# HumNet.net
KiCad netlist of a schematic drawn in Altium Designer
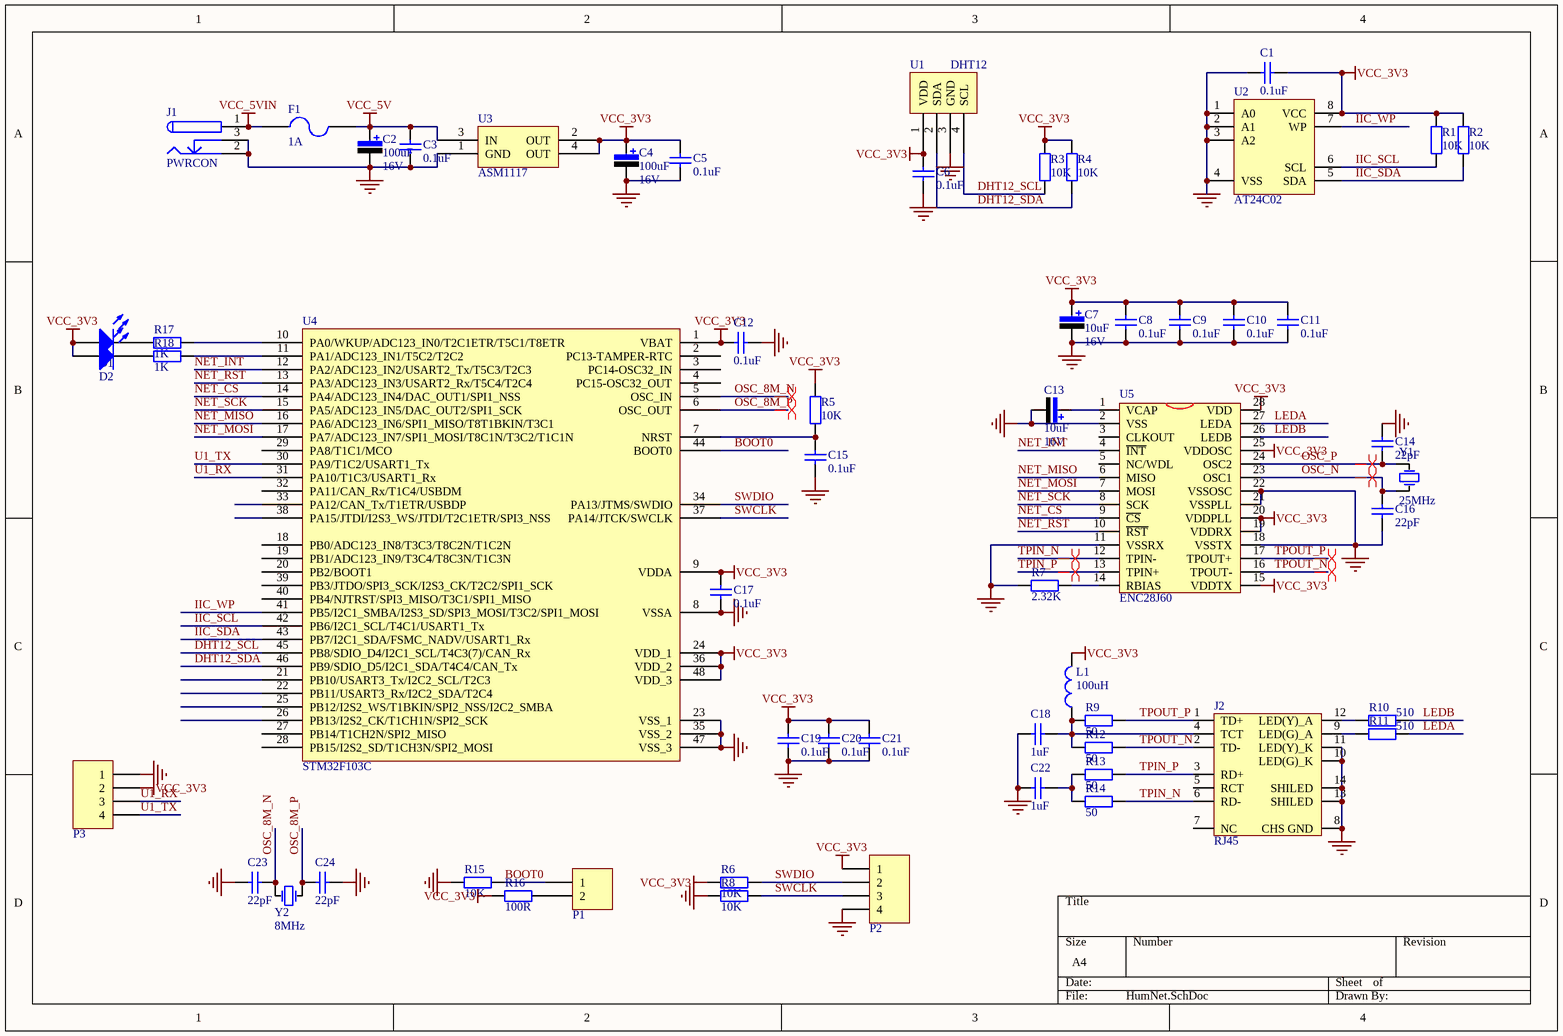
[diagram p0: HumNet.SchDoc]

(export (version "E")
  (design (tool "Eeschema 10.0.6"))
  (components
    (comp (ref "C1")
      (value "0.1uF")
      (footprint "C-RAD-0603")
      (description "无极性电容")
      (fields (field (name "Comment") "Cap") (field (name "PUBLISHER") "Altium Limited"))
      (libsource (lib "fszhang") (part "Cap"))
    )
    (comp (ref "C2")
      (value "100uF")
      (footprint "CAP-3528")
      (description "极性电解电容")
      (fields
        (field (name "VOL") "16V")
        (field (name "Comment") "Cap Pol")
        (field (name "PUBLISHER") "Altium Limited")
      )
      (libsource (lib "fszhang") (part "Cap Pol"))
    )
    (comp (ref "C3")
      (value "0.1uF")
      (footprint "C-RAD-0603")
      (description "无极性电容")
      (fields (field (name "Comment") "Cap") (field (name "PUBLISHER") "Altium Limited"))
      (libsource (lib "fszhang") (part "Cap"))
    )
    (comp (ref "C4")
      (value "100uF")
      (footprint "CAP-3528")
      (description "极性电解电容")
      (fields
        (field (name "VOL") "16V")
        (field (name "Comment") "Cap Pol")
        (field (name "PUBLISHER") "Altium Limited")
      )
      (libsource (lib "fszhang") (part "Cap Pol"))
    )
    (comp (ref "C5")
      (value "0.1uF")
      (footprint "C-RAD-0603")
      (description "无极性电容")
      (fields (field (name "Comment") "Cap") (field (name "PUBLISHER") "Altium Limited"))
      (libsource (lib "fszhang") (part "Cap"))
    )
    (comp (ref "C6")
      (value "0.1uF")
      (footprint "C-RAD-0603")
      (description "无极性电容")
      (fields (field (name "Comment") "Cap") (field (name "PUBLISHER") "Altium Limited"))
      (libsource (lib "fszhang") (part "Cap"))
    )
    (comp (ref "C7")
      (value "10uF")
      (footprint "CAP-3528")
      (description "极性电解电容")
      (fields
        (field (name "VOL") "16V")
        (field (name "Comment") "Cap Pol")
        (field (name "PUBLISHER") "Altium Limited")
      )
      (libsource (lib "fszhang") (part "Cap Pol"))
    )
    (comp (ref "C8")
      (value "0.1uF")
      (footprint "C-RAD-0603")
      (description "无极性电容")
      (fields (field (name "Comment") "Cap") (field (name "PUBLISHER") "Altium Limited"))
      (libsource (lib "fszhang") (part "Cap"))
    )
    (comp (ref "C9")
      (value "0.1uF")
      (footprint "C-RAD-0603")
      (description "无极性电容")
      (fields (field (name "Comment") "Cap") (field (name "PUBLISHER") "Altium Limited"))
      (libsource (lib "fszhang") (part "Cap"))
    )
    (comp (ref "C10")
      (value "0.1uF")
      (footprint "C-RAD-0603")
      (description "无极性电容")
      (fields (field (name "Comment") "Cap") (field (name "PUBLISHER") "Altium Limited"))
      (libsource (lib "fszhang") (part "Cap"))
    )
    (comp (ref "C11")
      (value "0.1uF")
      (footprint "C-RAD-0603")
      (description "无极性电容")
      (fields (field (name "Comment") "Cap") (field (name "PUBLISHER") "Altium Limited"))
      (libsource (lib "fszhang") (part "Cap"))
    )
    (comp (ref "C12")
      (value "0.1uF")
      (footprint "C-RAD-0603")
      (description "无极性电容")
      (fields (field (name "Comment") "Cap") (field (name "PUBLISHER") "Altium Limited"))
      (libsource (lib "fszhang") (part "Cap"))
    )
    (comp (ref "C13")
      (value "10uF")
      (footprint "CAP-3528")
      (description "极性电解电容")
      (fields
        (field (name "VOL") "16V")
        (field (name "Comment") "Cap Pol")
        (field (name "PUBLISHER") "Altium Limited")
      )
      (libsource (lib "") (part "Cap Pol_1"))
    )
    (comp (ref "C14")
      (value "22pF")
      (footprint "C-RAD-0603")
      (description "无极性电容")
      (fields (field (name "Comment") "Cap") (field (name "PUBLISHER") "Altium Limited"))
      (libsource (lib "fszhang") (part "Cap"))
    )
    (comp (ref "C15")
      (value "0.1uF")
      (footprint "C-RAD-0603")
      (description "无极性电容")
      (fields (field (name "Comment") "Cap") (field (name "PUBLISHER") "Altium Limited"))
      (libsource (lib "fszhang") (part "Cap"))
    )
    (comp (ref "C16")
      (value "22pF")
      (footprint "C-RAD-0603")
      (description "无极性电容")
      (fields (field (name "Comment") "Cap") (field (name "PUBLISHER") "Altium Limited"))
      (libsource (lib "fszhang") (part "Cap"))
    )
    (comp (ref "C17")
      (value "0.1uF")
      (footprint "C-RAD-0603")
      (description "无极性电容")
      (fields (field (name "Comment") "Cap") (field (name "PUBLISHER") "Altium Limited"))
      (libsource (lib "fszhang") (part "Cap"))
    )
    (comp (ref "C18")
      (value "1uF")
      (footprint "C-RAD-0603")
      (description "无极性电容")
      (fields (field (name "Comment") "Cap") (field (name "PUBLISHER") "Altium Limited"))
      (libsource (lib "fszhang") (part "Cap"))
    )
    (comp (ref "C19")
      (value "0.1uF")
      (footprint "C-RAD-0603")
      (description "无极性电容")
      (fields (field (name "Comment") "Cap") (field (name "PUBLISHER") "Altium Limited"))
      (libsource (lib "fszhang") (part "Cap"))
    )
    (comp (ref "C20")
      (value "0.1uF")
      (footprint "C-RAD-0603")
      (description "无极性电容")
      (fields (field (name "Comment") "Cap") (field (name "PUBLISHER") "Altium Limited"))
      (libsource (lib "fszhang") (part "Cap"))
    )
    (comp (ref "C21")
      (value "0.1uF")
      (footprint "C-RAD-0603")
      (description "无极性电容")
      (fields (field (name "Comment") "Cap") (field (name "PUBLISHER") "Altium Limited"))
      (libsource (lib "fszhang") (part "Cap"))
    )
    (comp (ref "C22")
      (value "1uF")
      (footprint "C-RAD-0603")
      (description "无极性电容")
      (fields (field (name "Comment") "Cap") (field (name "PUBLISHER") "Altium Limited"))
      (libsource (lib "fszhang") (part "Cap"))
    )
    (comp (ref "C23")
      (value "22pF")
      (footprint "C-RAD-0603")
      (description "无极性电容")
      (fields (field (name "Comment") "Cap") (field (name "PUBLISHER") "Altium Limited"))
      (libsource (lib "fszhang") (part "Cap"))
    )
    (comp (ref "C24")
      (value "22pF")
      (footprint "C-RAD-0603")
      (description "无极性电容")
      (fields (field (name "Comment") "Cap") (field (name "PUBLISHER") "Altium Limited"))
      (libsource (lib "fszhang") (part "Cap"))
    )
    (comp (ref "D1")
      (value "LED0")
      (footprint "LED_0805")
      (description "发光二极管")
      (fields (field (name "PUBLISHER") "Altium Limited"))
      (libsource (lib "fszhang") (part "LED0"))
    )
    (comp (ref "D2")
      (value "LED0")
      (footprint "LED_0805")
      (description "发光二极管")
      (fields (field (name "PUBLISHER") "Altium Limited"))
      (libsource (lib "fszhang") (part "LED0"))
    )
    (comp (ref "F1")
      (value "1A")
      (footprint "1812")
      (description "保险丝")
      (fields (field (name "Comment") "Fuse") (field (name "PUBLISHER") "Altium Limited"))
      (libsource (lib "fszhang") (part "Fuse 2"))
    )
    (comp (ref "J1")
      (value "PWRCON")
      (footprint "DC-005")
      (description "直流电源端子")
      (fields (field (name "PUBLISHER") "Altium Limited"))
      (libsource (lib "fszhang") (part "PWRCON"))
    )
    (comp (ref "J2")
      (value "RJ45")
      (footprint "HR911105A")
      (libsource (lib "ENC28J60网络模块封装库") (part "HR911105"))
    )
    (comp (ref "L1")
      (value "100uH")
      (footprint "1206")
      (description "电感")
      (fields (field (name "Comment") "Inductor") (field (name "PUBLISHER") "Altium Limited"))
      (libsource (lib "fszhang") (part "Inductor"))
    )
    (comp (ref "P1")
      (value "Header 2")
      (footprint "HDR2X1_A")
      (description "接插件")
      (fields (field (name "PUBLISHER") "Altium Limited"))
      (libsource (lib "fszhang") (part "Header 2"))
    )
    (comp (ref "P2")
      (value "Header 4")
      (footprint "HDR4X1_A")
      (description "接插件")
      (fields (field (name "PUBLISHER") "Altium Limited"))
      (libsource (lib "fszhang") (part "Header 4"))
    )
    (comp (ref "P3")
      (value "Header 4")
      (footprint "HDR4X1_A")
      (description "接插件")
      (fields (field (name "PUBLISHER") "Altium Limited"))
      (libsource (lib "") (part "Header 4_1"))
    )
    (comp (ref "R1")
      (value "10K")
      (footprint "0603-1")
      (description "贴片电阻")
      (fields (field (name "Comment") "Res1") (field (name "PUBLISHER") "Altium Limited"))
      (libsource (lib "") (part "Res1_1"))
    )
    (comp (ref "R2")
      (value "10K")
      (footprint "0603-1")
      (description "贴片电阻")
      (fields (field (name "Comment") "Res1") (field (name "PUBLISHER") "Altium Limited"))
      (libsource (lib "") (part "Res1_1"))
    )
    (comp (ref "R3")
      (value "10K")
      (footprint "0603-1")
      (description "贴片电阻")
      (fields (field (name "Comment") "Res1") (field (name "PUBLISHER") "Altium Limited"))
      (libsource (lib "") (part "Res1_1"))
    )
    (comp (ref "R4")
      (value "10K")
      (footprint "0603-1")
      (description "贴片电阻")
      (fields (field (name "Comment") "Res1") (field (name "PUBLISHER") "Altium Limited"))
      (libsource (lib "") (part "Res1_1"))
    )
    (comp (ref "R5")
      (value "10K")
      (footprint "0603-1")
      (description "贴片电阻")
      (fields (field (name "Comment") "Res1") (field (name "PUBLISHER") "Altium Limited"))
      (libsource (lib "") (part "Res1_1"))
    )
    (comp (ref "R6")
      (value "10K")
      (footprint "0603-1")
      (description "贴片电阻")
      (fields (field (name "Comment") "Res1") (field (name "PUBLISHER") "Altium Limited"))
      (libsource (lib "fszhang") (part "Res1"))
    )
    (comp (ref "R7")
      (value "2.32K")
      (footprint "0603-1")
      (description "贴片电阻")
      (fields (field (name "Comment") "Res1") (field (name "PUBLISHER") "Altium Limited"))
      (libsource (lib "fszhang") (part "Res1"))
    )
    (comp (ref "R8")
      (value "10K")
      (footprint "0603-1")
      (description "贴片电阻")
      (fields (field (name "Comment") "Res1") (field (name "PUBLISHER") "Altium Limited"))
      (libsource (lib "fszhang") (part "Res1"))
    )
    (comp (ref "R9")
      (value "50")
      (footprint "0603-1")
      (description "贴片电阻")
      (fields (field (name "Comment") "Res1") (field (name "PUBLISHER") "Altium Limited"))
      (libsource (lib "fszhang") (part "Res1"))
    )
    (comp (ref "R10")
      (value "510")
      (footprint "0603-1")
      (description "贴片电阻")
      (fields (field (name "Comment") "Res1") (field (name "PUBLISHER") "Altium Limited"))
      (libsource (lib "fszhang") (part "Res1"))
    )
    (comp (ref "R11")
      (value "510")
      (footprint "0603-1")
      (description "贴片电阻")
      (fields (field (name "Comment") "Res1") (field (name "PUBLISHER") "Altium Limited"))
      (libsource (lib "fszhang") (part "Res1"))
    )
    (comp (ref "R12")
      (value "50")
      (footprint "0603-1")
      (description "贴片电阻")
      (fields (field (name "Comment") "Res1") (field (name "PUBLISHER") "Altium Limited"))
      (libsource (lib "fszhang") (part "Res1"))
    )
    (comp (ref "R13")
      (value "50")
      (footprint "0603-1")
      (description "贴片电阻")
      (fields (field (name "Comment") "Res1") (field (name "PUBLISHER") "Altium Limited"))
      (libsource (lib "fszhang") (part "Res1"))
    )
    (comp (ref "R14")
      (value "50")
      (footprint "0603-1")
      (description "贴片电阻")
      (fields (field (name "Comment") "Res1") (field (name "PUBLISHER") "Altium Limited"))
      (libsource (lib "fszhang") (part "Res1"))
    )
    (comp (ref "R15")
      (value "10K")
      (footprint "0603-1")
      (description "贴片电阻")
      (fields (field (name "Comment") "Res1") (field (name "PUBLISHER") "Altium Limited"))
      (libsource (lib "fszhang") (part "Res1"))
    )
    (comp (ref "R16")
      (value "100R")
      (footprint "0603-1")
      (description "贴片电阻")
      (fields (field (name "Comment") "Res1") (field (name "PUBLISHER") "Altium Limited"))
      (libsource (lib "fszhang") (part "Res1"))
    )
    (comp (ref "R17")
      (value "1K")
      (footprint "0603-1")
      (description "贴片电阻")
      (fields (field (name "Comment") "Res1") (field (name "PUBLISHER") "Altium Limited"))
      (libsource (lib "fszhang") (part "Res1"))
    )
    (comp (ref "R18")
      (value "1K")
      (footprint "0603-1")
      (description "贴片电阻")
      (fields (field (name "Comment") "Res1") (field (name "PUBLISHER") "Altium Limited"))
      (libsource (lib "fszhang") (part "Res1"))
    )
    (comp (ref "U1") (value "DHT12") (footprint "DHT11") (libsource (lib "KS-D01") (part "DHT12")))
    (comp (ref "U2")
      (value "AT24C02")
      (footprint "SOIC8_N")
      (description "EEROM存储器")
      (libsource (lib "fszhang") (part "AT24C02"))
    )
    (comp (ref "U3")
      (value "ASM1117")
      (footprint "SOT-223")
      (description "3.3V稳压芯片")
      (libsource (lib "fszhang") (part "ASM1117"))
    )
    (comp (ref "U4")
      (value "STM32F103C")
      (footprint "LQFP-48_M")
      (description "STM32单片机48引脚")
      (libsource (lib "fszhang") (part "STM32F103C"))
    )
    (comp (ref "U5")
      (value "ENC28J60")
      (footprint "SSOP28")
      (libsource (lib "ENC28J60网络模块封装库") (part "ENC28J60"))
    )
    (comp (ref "Y1")
      (value "25MHz")
      (footprint "X-SM49")
      (description "晶振")
      (fields (field (name "Comment") "XTAL") (field (name "PUBLISHER") "Altium Limited"))
      (libsource (lib "fszhang") (part "XTAL"))
    )
    (comp (ref "Y2")
      (value "8MHz")
      (footprint "X-SM49")
      (description "晶振")
      (fields (field (name "Comment") "XTAL") (field (name "PUBLISHER") "Altium Limited"))
      (libsource (lib "fszhang") (part "XTAL"))
    )
  )
  (nets
    (net (code "1") (name "/BOOT0") (class "Default")
      (node (ref "P1") (pin "1") (pinfunction "1_1") (pintype "passive"))
      (node (ref "R15") (pin "2") (pinfunction "2_2") (pintype "passive"))
      (node (ref "U4") (pin "44") (pinfunction "BOOT0_44") (pintype "passive"))
    )
    (net (code "2") (name "/DHT12_SCL") (class "Default")
      (node (ref "R3") (pin "1") (pinfunction "1_1") (pintype "passive"))
      (node (ref "U1") (pin "4") (pinfunction "SCL_4") (pintype "passive"))
      (node (ref "U4") (pin "45") (pinfunction "PB8/SDIO_D4/I2C1_SCL/T4C3(7)/CAN_Rx_45") (pintype "passive"))
    )
    (net (code "3") (name "/DHT12_SDA") (class "Default")
      (node (ref "R4") (pin "1") (pinfunction "1_1") (pintype "passive"))
      (node (ref "U1") (pin "2") (pinfunction "SDA_2") (pintype "passive"))
      (node (ref "U4") (pin "46") (pinfunction "PB9/SDIO_D5/I2C1_SDA/T4C4/CAN_Tx_46") (pintype "passive"))
    )
    (net (code "4") (name "/IIC_SCL") (class "Default")
      (node (ref "R1") (pin "1") (pinfunction "1_1") (pintype "passive"))
      (node (ref "U2") (pin "6") (pinfunction "SCL_6") (pintype "passive"))
      (node (ref "U4") (pin "42") (pinfunction "PB6/I2C1_SCL/T4C1/USART1_Tx_42") (pintype "passive"))
    )
    (net (code "5") (name "/IIC_SDA") (class "Default")
      (node (ref "R2") (pin "1") (pinfunction "1_1") (pintype "passive"))
      (node (ref "U2") (pin "5") (pinfunction "SDA_5") (pintype "passive"))
      (node (ref "U4") (pin "43") (pinfunction "PB7/I2C1_SDA/FSMC_NADV/USART1_Rx_43") (pintype "passive"))
    )
    (net (code "6") (name "/IIC_WP") (class "Default")
      (node (ref "U2") (pin "7") (pinfunction "WP_7") (pintype "passive"))
      (node (ref "U4") (pin "41") (pinfunction "PB5/I2C1_SMBA/I2S3_SD/SPI3_MOSI/T3C2/SPI1_MOSI_41") (pintype "passive"))
    )
    (net (code "7") (name "/LEDA") (class "Default")
      (node (ref "R11") (pin "2") (pinfunction "2_2") (pintype "passive"))
      (node (ref "U5") (pin "27") (pinfunction "LEDA_27") (pintype "passive"))
    )
    (net (code "8") (name "/LEDB") (class "Default")
      (node (ref "R10") (pin "2") (pinfunction "2_2") (pintype "passive"))
      (node (ref "U5") (pin "26") (pinfunction "LEDB_26") (pintype "passive"))
    )
    (net (code "9") (name "/NET_CS") (class "Default")
      (node (ref "U4") (pin "14") (pinfunction "PA4/ADC123_IN4/DAC_OUT1/SPI1_NSS_14") (pintype "passive"))
      (node (ref "U5") (pin "9") (pinfunction "~{CS}_9") (pintype "passive"))
    )
    (net (code "10") (name "/NET_INT") (class "Default")
      (node (ref "U4") (pin "12") (pinfunction "PA2/ADC123_IN2/USART2_Tx/T5C3/T2C3_12") (pintype "passive"))
      (node (ref "U5") (pin "4") (pinfunction "~{INT}_4") (pintype "passive"))
    )
    (net (code "11") (name "/NET_MISO") (class "Default")
      (node (ref "U4") (pin "16") (pinfunction "PA6/ADC123_IN6/SPI1_MISO/T8T1BKIN/T3C1_16") (pintype "passive"))
      (node (ref "U5") (pin "6") (pinfunction "MISO_6") (pintype "passive"))
    )
    (net (code "12") (name "/NET_MOSI") (class "Default")
      (node (ref "U4") (pin "17") (pinfunction "PA7/ADC123_IN7/SPI1_MOSI/T8C1N/T3C2/T1C1N_17") (pintype "passive"))
      (node (ref "U5") (pin "7") (pinfunction "MOSI_7") (pintype "passive"))
    )
    (net (code "13") (name "/NET_RST") (class "Default")
      (node (ref "U4") (pin "13") (pinfunction "PA3/ADC123_IN3/USART2_Rx/T5C4/T2C4_13") (pintype "passive"))
      (node (ref "U5") (pin "10") (pinfunction "~{RST}_10") (pintype "passive"))
    )
    (net (code "14") (name "/NET_SCK") (class "Default")
      (node (ref "U4") (pin "15") (pinfunction "PA5/ADC123_IN5/DAC_OUT2/SPI1_SCK_15") (pintype "passive"))
      (node (ref "U5") (pin "8") (pinfunction "SCK_8") (pintype "passive"))
    )
    (net (code "15") (name "/OSC_8M_N") (class "Default")
      (node (ref "C23") (pin "2") (pinfunction "2_2") (pintype "passive"))
      (node (ref "U4") (pin "5") (pinfunction "OSC_IN_5") (pintype "passive"))
      (node (ref "Y2") (pin "2") (pinfunction "OSC2_2") (pintype "passive"))
    )
    (net (code "16") (name "/OSC_8M_P") (class "Default")
      (node (ref "C24") (pin "1") (pinfunction "1_1") (pintype "passive"))
      (node (ref "U4") (pin "6") (pinfunction "OSC_OUT_6") (pintype "passive"))
      (node (ref "Y2") (pin "1") (pinfunction "OSC1_1") (pintype "passive"))
    )
    (net (code "17") (name "/OSC_N") (class "Default")
      (node (ref "C16") (pin "1") (pinfunction "1_1") (pintype "passive"))
      (node (ref "U5") (pin "23") (pinfunction "OSC1_23") (pintype "passive"))
      (node (ref "Y1") (pin "2") (pinfunction "OSC2_2") (pintype "passive"))
    )
    (net (code "18") (name "/OSC_P") (class "Default")
      (node (ref "C14") (pin "2") (pinfunction "2_2") (pintype "passive"))
      (node (ref "U5") (pin "24") (pinfunction "OSC2_24") (pintype "passive"))
      (node (ref "Y1") (pin "1") (pinfunction "OSC1_1") (pintype "passive"))
    )
    (net (code "19") (name "/SWCLK") (class "Default")
      (node (ref "P2") (pin "3") (pinfunction "3_3") (pintype "passive"))
      (node (ref "R8") (pin "2") (pinfunction "2_2") (pintype "passive"))
      (node (ref "U4") (pin "37") (pinfunction "PA14/JTCK/SWCLK_37") (pintype "passive"))
    )
    (net (code "20") (name "/SWDIO") (class "Default")
      (node (ref "P2") (pin "2") (pinfunction "2_2") (pintype "passive"))
      (node (ref "R6") (pin "2") (pinfunction "2_2") (pintype "passive"))
      (node (ref "U4") (pin "34") (pinfunction "PA13/JTMS/SWDIO_34") (pintype "passive"))
    )
    (net (code "21") (name "/TPIN_N") (class "Default")
      (node (ref "J2") (pin "6") (pinfunction "RD-_6") (pintype "passive"))
      (node (ref "R14") (pin "2") (pinfunction "2_2") (pintype "passive"))
      (node (ref "U5") (pin "12") (pinfunction "TPIN-_12") (pintype "passive"))
    )
    (net (code "22") (name "/TPIN_P") (class "Default")
      (node (ref "J2") (pin "3") (pinfunction "RD+_3") (pintype "passive"))
      (node (ref "R13") (pin "2") (pinfunction "2_2") (pintype "passive"))
      (node (ref "U5") (pin "13") (pinfunction "TPIN+_13") (pintype "passive"))
    )
    (net (code "23") (name "/TPOUT_N") (class "Default")
      (node (ref "J2") (pin "2") (pinfunction "TD-_2") (pintype "passive"))
      (node (ref "R12") (pin "2") (pinfunction "2_2") (pintype "passive"))
      (node (ref "U5") (pin "16") (pinfunction "TPOUT-_16") (pintype "passive"))
    )
    (net (code "24") (name "/TPOUT_P") (class "Default")
      (node (ref "J2") (pin "1") (pinfunction "TD+_1") (pintype "passive"))
      (node (ref "R9") (pin "2") (pinfunction "2_2") (pintype "passive"))
      (node (ref "U5") (pin "17") (pinfunction "TPOUT+_17") (pintype "passive"))
    )
    (net (code "25") (name "/U1_RX") (class "Default")
      (node (ref "P3") (pin "3") (pinfunction "3_3") (pintype "passive"))
      (node (ref "U4") (pin "31") (pinfunction "PA10/T1C3/USART1_Rx_31") (pintype "passive"))
    )
    (net (code "26") (name "/U1_TX") (class "Default")
      (node (ref "P3") (pin "4") (pinfunction "4_4") (pintype "passive"))
      (node (ref "U4") (pin "30") (pinfunction "PA9/T1C2/USART1_Tx_30") (pintype "passive"))
    )
    (net (code "27") (name "GND") (class "Default")
      (node (ref "C1") (pin "1") (pinfunction "1_1") (pintype "passive"))
      (node (ref "C10") (pin "1") (pinfunction "1_1") (pintype "passive"))
      (node (ref "C11") (pin "1") (pinfunction "1_1") (pintype "passive"))
      (node (ref "C12") (pin "1") (pinfunction "1_1") (pintype "passive"))
      (node (ref "C13") (pin "2") (pinfunction "2_2") (pintype "passive"))
      (node (ref "C14") (pin "1") (pinfunction "1_1") (pintype "passive"))
      (node (ref "C15") (pin "1") (pinfunction "1_1") (pintype "passive"))
      (node (ref "C16") (pin "2") (pinfunction "2_2") (pintype "passive"))
      (node (ref "C17") (pin "1") (pinfunction "1_1") (pintype "passive"))
      (node (ref "C18") (pin "2") (pinfunction "2_2") (pintype "passive"))
      (node (ref "C19") (pin "1") (pinfunction "1_1") (pintype "passive"))
      (node (ref "C2") (pin "2") (pinfunction "2_2") (pintype "passive"))
      (node (ref "C20") (pin "1") (pinfunction "1_1") (pintype "passive"))
      (node (ref "C21") (pin "1") (pinfunction "1_1") (pintype "passive"))
      (node (ref "C22") (pin "2") (pinfunction "2_2") (pintype "passive"))
      (node (ref "C23") (pin "1") (pinfunction "1_1") (pintype "passive"))
      (node (ref "C24") (pin "2") (pinfunction "2_2") (pintype "passive"))
      (node (ref "C3") (pin "1") (pinfunction "1_1") (pintype "passive"))
      (node (ref "C4") (pin "2") (pinfunction "2_2") (pintype "passive"))
      (node (ref "C5") (pin "1") (pinfunction "1_1") (pintype "passive"))
      (node (ref "C6") (pin "1") (pinfunction "1_1") (pintype "passive"))
      (node (ref "C7") (pin "2") (pinfunction "2_2") (pintype "passive"))
      (node (ref "C8") (pin "1") (pinfunction "1_1") (pintype "passive"))
      (node (ref "C9") (pin "1") (pinfunction "1_1") (pintype "passive"))
      (node (ref "J1") (pin "2") (pinfunction "2_2") (pintype "power_in"))
      (node (ref "J1") (pin "3") (pinfunction "3_3") (pintype "power_in"))
      (node (ref "J2") (pin "10") (pinfunction "LED(G)_K_10") (pintype "passive"))
      (node (ref "J2") (pin "11") (pinfunction "LED(Y)_K_11") (pintype "passive"))
      (node (ref "J2") (pin "13") (pinfunction "SHILED_13") (pintype "passive"))
      (node (ref "J2") (pin "14") (pinfunction "SHILED_14") (pintype "passive"))
      (node (ref "J2") (pin "8") (pinfunction "CHS_GND_8") (pintype "passive"))
      (node (ref "P2") (pin "4") (pinfunction "4_4") (pintype "passive"))
      (node (ref "P3") (pin "1") (pinfunction "1_1") (pintype "passive"))
      (node (ref "R15") (pin "1") (pinfunction "1_1") (pintype "passive"))
      (node (ref "R7") (pin "1") (pinfunction "1_1") (pintype "passive"))
      (node (ref "R8") (pin "1") (pinfunction "1_1") (pintype "passive"))
      (node (ref "U1") (pin "3") (pinfunction "GND_3") (pintype "passive"))
      (node (ref "U2") (pin "1") (pinfunction "A0_1") (pintype "passive"))
      (node (ref "U2") (pin "2") (pinfunction "A1_2") (pintype "passive"))
      (node (ref "U2") (pin "3") (pinfunction "A2_3") (pintype "passive"))
      (node (ref "U2") (pin "4") (pinfunction "VSS_4") (pintype "passive"))
      (node (ref "U3") (pin "1") (pinfunction "GND_1") (pintype "passive"))
      (node (ref "U4") (pin "23") (pinfunction "VSS_1_23") (pintype "passive"))
      (node (ref "U4") (pin "35") (pinfunction "VSS_2_35") (pintype "passive"))
      (node (ref "U4") (pin "47") (pinfunction "VSS_3_47") (pintype "passive"))
      (node (ref "U4") (pin "8") (pinfunction "VSSA_8") (pintype "passive"))
      (node (ref "U5") (pin "11") (pinfunction "VSSRX_11") (pintype "passive"))
      (node (ref "U5") (pin "18") (pinfunction "VSSTX_18") (pintype "passive"))
      (node (ref "U5") (pin "2") (pinfunction "VSS_2") (pintype "passive"))
      (node (ref "U5") (pin "21") (pinfunction "VSSPLL_21") (pintype "passive"))
      (node (ref "U5") (pin "22") (pinfunction "VSSOSC_22") (pintype "passive"))
    )
    (net (code "28") (name "Net-(C22-Pad1)") (class "Default")
      (node (ref "C22") (pin "1") (pinfunction "1_1") (pintype "passive"))
      (node (ref "R13") (pin "1") (pinfunction "1_1") (pintype "passive"))
      (node (ref "R14") (pin "1") (pinfunction "1_1") (pintype "passive"))
    )
    (net (code "29") (name "Net-(D1-K)") (class "Default")
      (node (ref "D1") (pin "2") (pinfunction "K_2") (pintype "passive"))
      (node (ref "R17") (pin "1") (pinfunction "1_1") (pintype "passive"))
    )
    (net (code "30") (name "Net-(D2-K)") (class "Default")
      (node (ref "D2") (pin "2") (pinfunction "K_2") (pintype "passive"))
      (node (ref "R18") (pin "1") (pinfunction "1_1") (pintype "passive"))
    )
    (net (code "31") (name "Net-(J2-LED(G)_A)") (class "Default")
      (node (ref "J2") (pin "9") (pinfunction "LED(G)_A_9") (pintype "passive"))
      (node (ref "R11") (pin "1") (pinfunction "1_1") (pintype "passive"))
    )
    (net (code "32") (name "Net-(J2-LED(Y)_A)") (class "Default")
      (node (ref "J2") (pin "12") (pinfunction "LED(Y)_A_12") (pintype "passive"))
      (node (ref "R10") (pin "1") (pinfunction "1_1") (pintype "passive"))
    )
    (net (code "33") (name "Net-(J2-TCT)") (class "Default")
      (node (ref "C18") (pin "1") (pinfunction "1_1") (pintype "passive"))
      (node (ref "J2") (pin "4") (pinfunction "TCT_4") (pintype "passive"))
      (node (ref "L1") (pin "1") (pinfunction "1_1") (pintype "passive"))
      (node (ref "R12") (pin "1") (pinfunction "1_1") (pintype "passive"))
      (node (ref "R9") (pin "1") (pinfunction "1_1") (pintype "passive"))
    )
    (net (code "34") (name "Net-(P1-Pad2)") (class "Default")
      (node (ref "P1") (pin "2") (pinfunction "2_2") (pintype "passive"))
      (node (ref "R16") (pin "2") (pinfunction "2_2") (pintype "passive"))
    )
    (net (code "35") (name "Net-(U4-NRST)") (class "Default")
      (node (ref "C15") (pin "2") (pinfunction "2_2") (pintype "passive"))
      (node (ref "R5") (pin "1") (pinfunction "1_1") (pintype "passive"))
      (node (ref "U4") (pin "7") (pinfunction "NRST_7") (pintype "passive"))
    )
    (net (code "36") (name "Net-(U4-PA0{slash}WKUP{slash}ADC123_IN0{slash}T2C1ETR{slash}T5C1{slash}T8ETR)") (class "Default")
      (node (ref "R17") (pin "2") (pinfunction "2_2") (pintype "passive"))
      (node (ref "U4") (pin "10") (pinfunction "PA0/WKUP/ADC123_IN0/T2C1ETR/T5C1/T8ETR_10") (pintype "passive"))
    )
    (net (code "37") (name "Net-(U4-PA1{slash}ADC123_IN1{slash}T5C2{slash}T2C2)") (class "Default")
      (node (ref "R18") (pin "2") (pinfunction "2_2") (pintype "passive"))
      (node (ref "U4") (pin "11") (pinfunction "PA1/ADC123_IN1/T5C2/T2C2_11") (pintype "passive"))
    )
    (net (code "38") (name "Net-(U5-RBIAS)") (class "Default")
      (node (ref "R7") (pin "2") (pinfunction "2_2") (pintype "passive"))
      (node (ref "U5") (pin "14") (pinfunction "RBIAS_14") (pintype "passive"))
    )
    (net (code "39") (name "Net-(U5-VCAP)") (class "Default")
      (node (ref "C13") (pin "1") (pinfunction "1_1") (pintype "passive"))
      (node (ref "U5") (pin "1") (pinfunction "VCAP_1") (pintype "passive"))
    )
    (net (code "40") (name "VCC_3V3") (class "Default")
      (node (ref "C1") (pin "2") (pinfunction "2_2") (pintype "passive"))
      (node (ref "C10") (pin "2") (pinfunction "2_2") (pintype "passive"))
      (node (ref "C11") (pin "2") (pinfunction "2_2") (pintype "passive"))
      (node (ref "C12") (pin "2") (pinfunction "2_2") (pintype "passive"))
      (node (ref "C17") (pin "2") (pinfunction "2_2") (pintype "passive"))
      (node (ref "C19") (pin "2") (pinfunction "2_2") (pintype "passive"))
      (node (ref "C20") (pin "2") (pinfunction "2_2") (pintype "passive"))
      (node (ref "C21") (pin "2") (pinfunction "2_2") (pintype "passive"))
      (node (ref "C4") (pin "1") (pinfunction "1_1") (pintype "passive"))
      (node (ref "C5") (pin "2") (pinfunction "2_2") (pintype "passive"))
      (node (ref "C6") (pin "2") (pinfunction "2_2") (pintype "passive"))
      (node (ref "C7") (pin "1") (pinfunction "1_1") (pintype "passive"))
      (node (ref "C8") (pin "2") (pinfunction "2_2") (pintype "passive"))
      (node (ref "C9") (pin "2") (pinfunction "2_2") (pintype "passive"))
      (node (ref "D1") (pin "1") (pinfunction "A_1") (pintype "passive"))
      (node (ref "D2") (pin "1") (pinfunction "A_1") (pintype "passive"))
      (node (ref "L1") (pin "2") (pinfunction "2_2") (pintype "passive"))
      (node (ref "P2") (pin "1") (pinfunction "1_1") (pintype "passive"))
      (node (ref "P3") (pin "2") (pinfunction "2_2") (pintype "passive"))
      (node (ref "R1") (pin "2") (pinfunction "2_2") (pintype "passive"))
      (node (ref "R16") (pin "1") (pinfunction "1_1") (pintype "passive"))
      (node (ref "R2") (pin "2") (pinfunction "2_2") (pintype "passive"))
      (node (ref "R3") (pin "2") (pinfunction "2_2") (pintype "passive"))
      (node (ref "R4") (pin "2") (pinfunction "2_2") (pintype "passive"))
      (node (ref "R5") (pin "2") (pinfunction "2_2") (pintype "passive"))
      (node (ref "R6") (pin "1") (pinfunction "1_1") (pintype "passive"))
      (node (ref "U1") (pin "1") (pinfunction "VDD_1") (pintype "passive"))
      (node (ref "U2") (pin "8") (pinfunction "VCC_8") (pintype "passive"))
      (node (ref "U3") (pin "2") (pinfunction "OUT_2") (pintype "passive"))
      (node (ref "U3") (pin "4") (pinfunction "OUT_4") (pintype "passive"))
      (node (ref "U4") (pin "1") (pinfunction "VBAT_1") (pintype "passive"))
      (node (ref "U4") (pin "24") (pinfunction "VDD_1_24") (pintype "passive"))
      (node (ref "U4") (pin "36") (pinfunction "VDD_2_36") (pintype "passive"))
      (node (ref "U4") (pin "48") (pinfunction "VDD_3_48") (pintype "passive"))
      (node (ref "U4") (pin "9") (pinfunction "VDDA_9") (pintype "passive"))
      (node (ref "U5") (pin "15") (pinfunction "VDDTX_15") (pintype "passive"))
      (node (ref "U5") (pin "19") (pinfunction "VDDRX_19") (pintype "passive"))
      (node (ref "U5") (pin "20") (pinfunction "VDDPLL_20") (pintype "passive"))
      (node (ref "U5") (pin "25") (pinfunction "VDDOSC_25") (pintype "passive"))
      (node (ref "U5") (pin "28") (pinfunction "VDD_28") (pintype "passive"))
    )
    (net (code "41") (name "VCC_5V") (class "Default")
      (node (ref "C2") (pin "1") (pinfunction "1_1") (pintype "passive"))
      (node (ref "C3") (pin "2") (pinfunction "2_2") (pintype "passive"))
      (node (ref "F1") (pin "2") (pinfunction "2_2") (pintype "passive"))
      (node (ref "U3") (pin "3") (pinfunction "IN_3") (pintype "passive"))
    )
    (net (code "42") (name "VCC_5VIN") (class "Default")
      (node (ref "F1") (pin "1") (pinfunction "1_1") (pintype "passive"))
      (node (ref "J1") (pin "1") (pinfunction "1_1") (pintype "power_in"))
    )
    (net (code "43") (name "unconnected-(J2-NC-Pad7)") (class "Default")
      (node (ref "J2") (pin "7") (pinfunction "NC_7") (pintype "passive"))
    )
    (net (code "44") (name "unconnected-(J2-RCT-Pad5)") (class "Default")
      (node (ref "J2") (pin "5") (pinfunction "RCT_5") (pintype "passive"))
    )
    (net (code "45") (name "unconnected-(U4-PA8{slash}T1C1{slash}MCO-Pad29)") (class "Default")
      (node (ref "U4") (pin "29") (pinfunction "PA8/T1C1/MCO_29") (pintype "passive"))
    )
    (net (code "46") (name "unconnected-(U4-PA11{slash}CAN_Rx{slash}T1C4{slash}USBDM-Pad32)") (class "Default")
      (node (ref "U4") (pin "32") (pinfunction "PA11/CAN_Rx/T1C4/USBDM_32") (pintype "passive"))
    )
    (net (code "47") (name "unconnected-(U4-PA12{slash}CAN_Tx{slash}T1ETR{slash}USBDP-Pad33)") (class "Default")
      (node (ref "U4") (pin "33") (pinfunction "PA12/CAN_Tx/T1ETR/USBDP_33") (pintype "passive"))
    )
    (net (code "48") (name "unconnected-(U4-PA15{slash}JTDI{slash}I2S3_WS{slash}JTDI{slash}T2C1ETR{slash}SPI3_NSS-Pad38)") (class "Default")
      (node (ref "U4") (pin "38") (pinfunction "PA15/JTDI/I2S3_WS/JTDI/T2C1ETR/SPI3_NSS_38") (pintype "passive"))
    )
    (net (code "49") (name "unconnected-(U4-PB0{slash}ADC123_IN8{slash}T3C3{slash}T8C2N{slash}T1C2N-Pad18)") (class "Default")
      (node (ref "U4") (pin "18") (pinfunction "PB0/ADC123_IN8/T3C3/T8C2N/T1C2N_18") (pintype "passive"))
    )
    (net (code "50") (name "unconnected-(U4-PB1{slash}ADC123_IN9{slash}T3C4{slash}T8C3N{slash}T1C3N-Pad19)") (class "Default")
      (node (ref "U4") (pin "19") (pinfunction "PB1/ADC123_IN9/T3C4/T8C3N/T1C3N_19") (pintype "passive"))
    )
    (net (code "51") (name "unconnected-(U4-PB2{slash}BOOT1-Pad20)") (class "Default")
      (node (ref "U4") (pin "20") (pinfunction "PB2/BOOT1_20") (pintype "passive"))
    )
    (net (code "52") (name "unconnected-(U4-PB3{slash}JTDO{slash}SPI3_SCK{slash}I2S3_CK{slash}T2C2{slash}SPI1_SCK-Pad39)") (class "Default")
      (node (ref "U4") (pin "39") (pinfunction "PB3/JTDO/SPI3_SCK/I2S3_CK/T2C2/SPI1_SCK_39") (pintype "passive"))
    )
    (net (code "53") (name "unconnected-(U4-PB4{slash}NJTRST{slash}SPI3_MISO{slash}T3C1{slash}SPI1_MISO-Pad40)") (class "Default")
      (node (ref "U4") (pin "40") (pinfunction "PB4/NJTRST/SPI3_MISO/T3C1/SPI1_MISO_40") (pintype "passive"))
    )
    (net (code "54") (name "unconnected-(U4-PB10{slash}USART3_Tx{slash}I2C2_SCL{slash}T2C3-Pad21)") (class "Default")
      (node (ref "U4") (pin "21") (pinfunction "PB10/USART3_Tx/I2C2_SCL/T2C3_21") (pintype "passive"))
    )
    (net (code "55") (name "unconnected-(U4-PB11{slash}USART3_Rx{slash}I2C2_SDA{slash}T2C4-Pad22)") (class "Default")
      (node (ref "U4") (pin "22") (pinfunction "PB11/USART3_Rx/I2C2_SDA/T2C4_22") (pintype "passive"))
    )
    (net (code "56") (name "unconnected-(U4-PB12{slash}I2S2_WS{slash}T1BKIN{slash}SPI2_NSS{slash}I2C2_SMBA-Pad25)") (class "Default")
      (node (ref "U4") (pin "25") (pinfunction "PB12/I2S2_WS/T1BKIN/SPI2_NSS/I2C2_SMBA_25") (pintype "passive"))
    )
    (net (code "57") (name "unconnected-(U4-PB13{slash}I2S2_CK{slash}T1CH1N{slash}SPI2_SCK-Pad26)") (class "Default")
      (node (ref "U4") (pin "26") (pinfunction "PB13/I2S2_CK/T1CH1N/SPI2_SCK_26") (pintype "passive"))
    )
    (net (code "58") (name "unconnected-(U4-PB14{slash}T1CH2N{slash}SPI2_MISO-Pad27)") (class "Default")
      (node (ref "U4") (pin "27") (pinfunction "PB14/T1CH2N/SPI2_MISO_27") (pintype "passive"))
    )
    (net (code "59") (name "unconnected-(U4-PB15{slash}I2S2_SD{slash}T1CH3N{slash}SPI2_MOSI-Pad28)") (class "Default")
      (node (ref "U4") (pin "28") (pinfunction "PB15/I2S2_SD/T1CH3N/SPI2_MOSI_28") (pintype "passive"))
    )
    (net (code "60") (name "unconnected-(U4-PC13-TAMPER-RTC-Pad2)") (class "Default")
      (node (ref "U4") (pin "2") (pinfunction "PC13-TAMPER-RTC_2") (pintype "passive"))
    )
    (net (code "61") (name "unconnected-(U4-PC14-OSC32_IN-Pad3)") (class "Default")
      (node (ref "U4") (pin "3") (pinfunction "PC14-OSC32_IN_3") (pintype "passive"))
    )
    (net (code "62") (name "unconnected-(U4-PC15-OSC32_OUT-Pad4)") (class "Default")
      (node (ref "U4") (pin "4") (pinfunction "PC15-OSC32_OUT_4") (pintype "passive"))
    )
    (net (code "63") (name "unconnected-(U5-CLKOUT-Pad3)") (class "Default")
      (node (ref "U5") (pin "3") (pinfunction "CLKOUT_3") (pintype "passive"))
    )
    (net (code "64") (name "unconnected-(U5-NC{slash}WDL-Pad5)") (class "Default")
      (node (ref "U5") (pin "5") (pinfunction "NC/WDL_5") (pintype "passive"))
    )
  )
)
